# current_signal_adaptation_3.net
KiCad netlist of a schematic drawn in Altium Designer
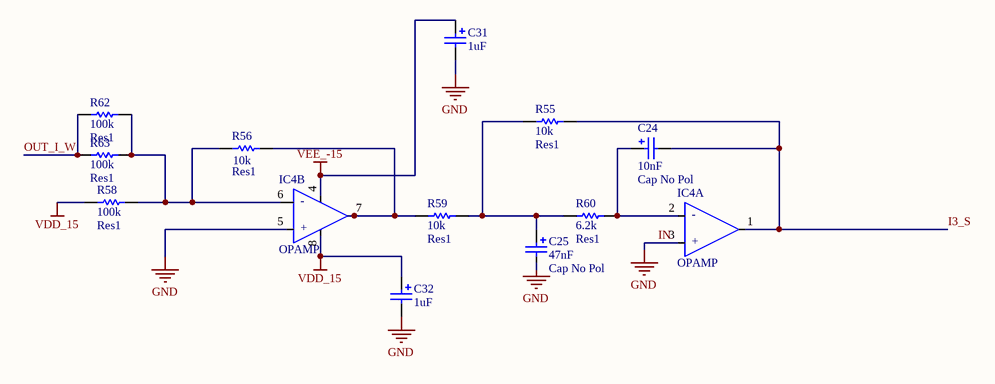
[diagram p0: current_signal_adaptation_3.SchDoc]

(export (version "E")
  (design (tool "Eeschema 10.0.6"))
  (components
    (comp (ref "C24")
      (value "Cap No Pol")
      (footprint "RAD-0.1")
      (description "Polarized Capacitor (Radial)")
      (fields (field (name "ALTIUM_VALUE") "10nF") (field (name "PUBLISHER") "Altium Limited"))
      (libsource (lib "LABSTEPS_Project") (part "Cap No Pol"))
    )
    (comp (ref "C25")
      (value "Cap No Pol")
      (footprint "RAD-0.1")
      (description "Polarized Capacitor (Radial)")
      (fields (field (name "ALTIUM_VALUE") "47nF") (field (name "PUBLISHER") "Altium Limited"))
      (libsource (lib "LABSTEPS_Project") (part "Cap No Pol"))
    )
    (comp (ref "C31")
      (value "1uF")
      (footprint "RAD-0.1")
      (description "Polarized Capacitor (Radial)")
      (fields (field (name "Comment") "Cap No Pol") (field (name "PUBLISHER") "Altium Limited"))
      (libsource (lib "LABSTEPS_Project") (part "Cap No Pol"))
    )
    (comp (ref "C32")
      (value "1uF")
      (footprint "RAD-0.1")
      (description "Polarized Capacitor (Radial)")
      (fields (field (name "Comment") "Cap No Pol") (field (name "PUBLISHER") "Altium Limited"))
      (libsource (lib "LABSTEPS_Project") (part "Cap No Pol"))
    )
    (comp (ref "IC4")
      (value "OPAMP")
      (footprint "DIP-8")
      (description "ADTL082")
      (libsource (lib "LABSTEPS_Project") (part "ADTL082"))
    )
    (comp (ref "R55")
      (value "Res1")
      (footprint "AXIAL-0.4")
      (description "Resistor")
      (fields (field (name "ALTIUM_VALUE") "10k") (field (name "PUBLISHER") "Altium Limited"))
      (libsource (lib "LABSTEPS_Project") (part "Res1"))
    )
    (comp (ref "R56")
      (value "Res1")
      (footprint "AXIAL-0.4")
      (description "Resistor")
      (fields (field (name "ALTIUM_VALUE") "10k") (field (name "PUBLISHER") "Altium Limited"))
      (libsource (lib "LABSTEPS_Project") (part "Res1"))
    )
    (comp (ref "R58")
      (value "Res1")
      (footprint "AXIAL-0.4")
      (description "Resistor")
      (fields (field (name "ALTIUM_VALUE") "100k") (field (name "PUBLISHER") "Altium Limited"))
      (libsource (lib "LABSTEPS_Project") (part "Res1"))
    )
    (comp (ref "R59")
      (value "Res1")
      (footprint "AXIAL-0.4")
      (description "Resistor")
      (fields (field (name "ALTIUM_VALUE") "10k") (field (name "PUBLISHER") "Altium Limited"))
      (libsource (lib "LABSTEPS_Project") (part "Res1"))
    )
    (comp (ref "R60")
      (value "Res1")
      (footprint "AXIAL-0.4")
      (description "Resistor")
      (fields (field (name "ALTIUM_VALUE") "6.2k") (field (name "PUBLISHER") "Altium Limited"))
      (libsource (lib "LABSTEPS_Project") (part "Res1"))
    )
    (comp (ref "R62")
      (value "Res1")
      (footprint "AXIAL-0.4")
      (description "Resistor")
      (fields (field (name "ALTIUM_VALUE") "100k") (field (name "PUBLISHER") "Altium Limited"))
      (libsource (lib "LABSTEPS_Project") (part "Res1"))
    )
    (comp (ref "R63")
      (value "Res1")
      (footprint "AXIAL-0.4")
      (description "Resistor")
      (fields (field (name "ALTIUM_VALUE") "100k") (field (name "PUBLISHER") "Altium Limited"))
      (libsource (lib "LABSTEPS_Project") (part "Res1"))
    )
  )
  (nets
    (net (code "1") (name "/I3_S") (class "Default")
      (node (ref "C24") (pin "2") (pinfunction "2_2") (pintype "passive"))
      (node (ref "IC4") (pin "1") (pinfunction "OUT_A_1") (pintype "passive"))
      (node (ref "R55") (pin "2") (pinfunction "2_2") (pintype "passive"))
    )
    (net (code "2") (name "/OUT_I_W") (class "Default")
      (node (ref "R62") (pin "1") (pinfunction "1_1") (pintype "passive"))
      (node (ref "R63") (pin "1") (pinfunction "1_1") (pintype "passive"))
    )
    (net (code "3") (name "GND") (class "Default")
      (node (ref "C25") (pin "2") (pinfunction "2_2") (pintype "passive"))
      (node (ref "C31") (pin "2") (pinfunction "2_2") (pintype "passive"))
      (node (ref "C32") (pin "2") (pinfunction "2_2") (pintype "passive"))
      (node (ref "IC4") (pin "3") (pinfunction "IN_A_+_3") (pintype "passive"))
      (node (ref "IC4") (pin "5") (pinfunction "IN_B_+_5") (pintype "passive"))
    )
    (net (code "4") (name "Net-(C25-Pad1)") (class "Default")
      (node (ref "C25") (pin "1") (pinfunction "1_1") (pintype "passive"))
      (node (ref "R55") (pin "1") (pinfunction "1_1") (pintype "passive"))
      (node (ref "R59") (pin "2") (pinfunction "2_2") (pintype "passive"))
      (node (ref "R60") (pin "1") (pinfunction "1_1") (pintype "passive"))
    )
    (net (code "5") (name "Net-(IC4A-IN_A_-)") (class "Default")
      (node (ref "C24") (pin "1") (pinfunction "1_1") (pintype "passive"))
      (node (ref "IC4") (pin "2") (pinfunction "IN_A_-_2") (pintype "passive"))
      (node (ref "R60") (pin "2") (pinfunction "2_2") (pintype "passive"))
    )
    (net (code "6") (name "Net-(IC4B-OUT_B)") (class "Default")
      (node (ref "IC4") (pin "7") (pinfunction "OUT_B_7") (pintype "passive"))
      (node (ref "R56") (pin "2") (pinfunction "2_2") (pintype "passive"))
      (node (ref "R59") (pin "1") (pinfunction "1_1") (pintype "passive"))
    )
    (net (code "7") (name "Net-(R56-Pad1)") (class "Default")
      (node (ref "R56") (pin "1") (pinfunction "1_1") (pintype "passive"))
      (node (ref "R58") (pin "2") (pinfunction "2_2") (pintype "passive"))
      (node (ref "R62") (pin "2") (pinfunction "2_2") (pintype "passive"))
      (node (ref "R63") (pin "2") (pinfunction "2_2") (pintype "passive"))
    )
    (net (code "8") (name "VDD_15") (class "Default")
      (node (ref "C32") (pin "1") (pinfunction "1_1") (pintype "passive"))
      (node (ref "IC4") (pin "8") (pinfunction "V+_8") (pintype "passive"))
      (node (ref "R58") (pin "1") (pinfunction "1_1") (pintype "passive"))
    )
    (net (code "9") (name "VEE_-15") (class "Default")
      (node (ref "C31") (pin "1") (pinfunction "1_1") (pintype "passive"))
      (node (ref "IC4") (pin "4") (pinfunction "-V_4") (pintype "passive"))
    )
    (net (code "10") (name "unconnected-(IC4B-IN_B_--Pad6)") (class "Default")
      (node (ref "IC4") (pin "6") (pinfunction "IN_B_-_6") (pintype "passive"))
    )
  )
)
